# akabeacon_square.net
KiCad netlist of a schematic drawn in EAGLE
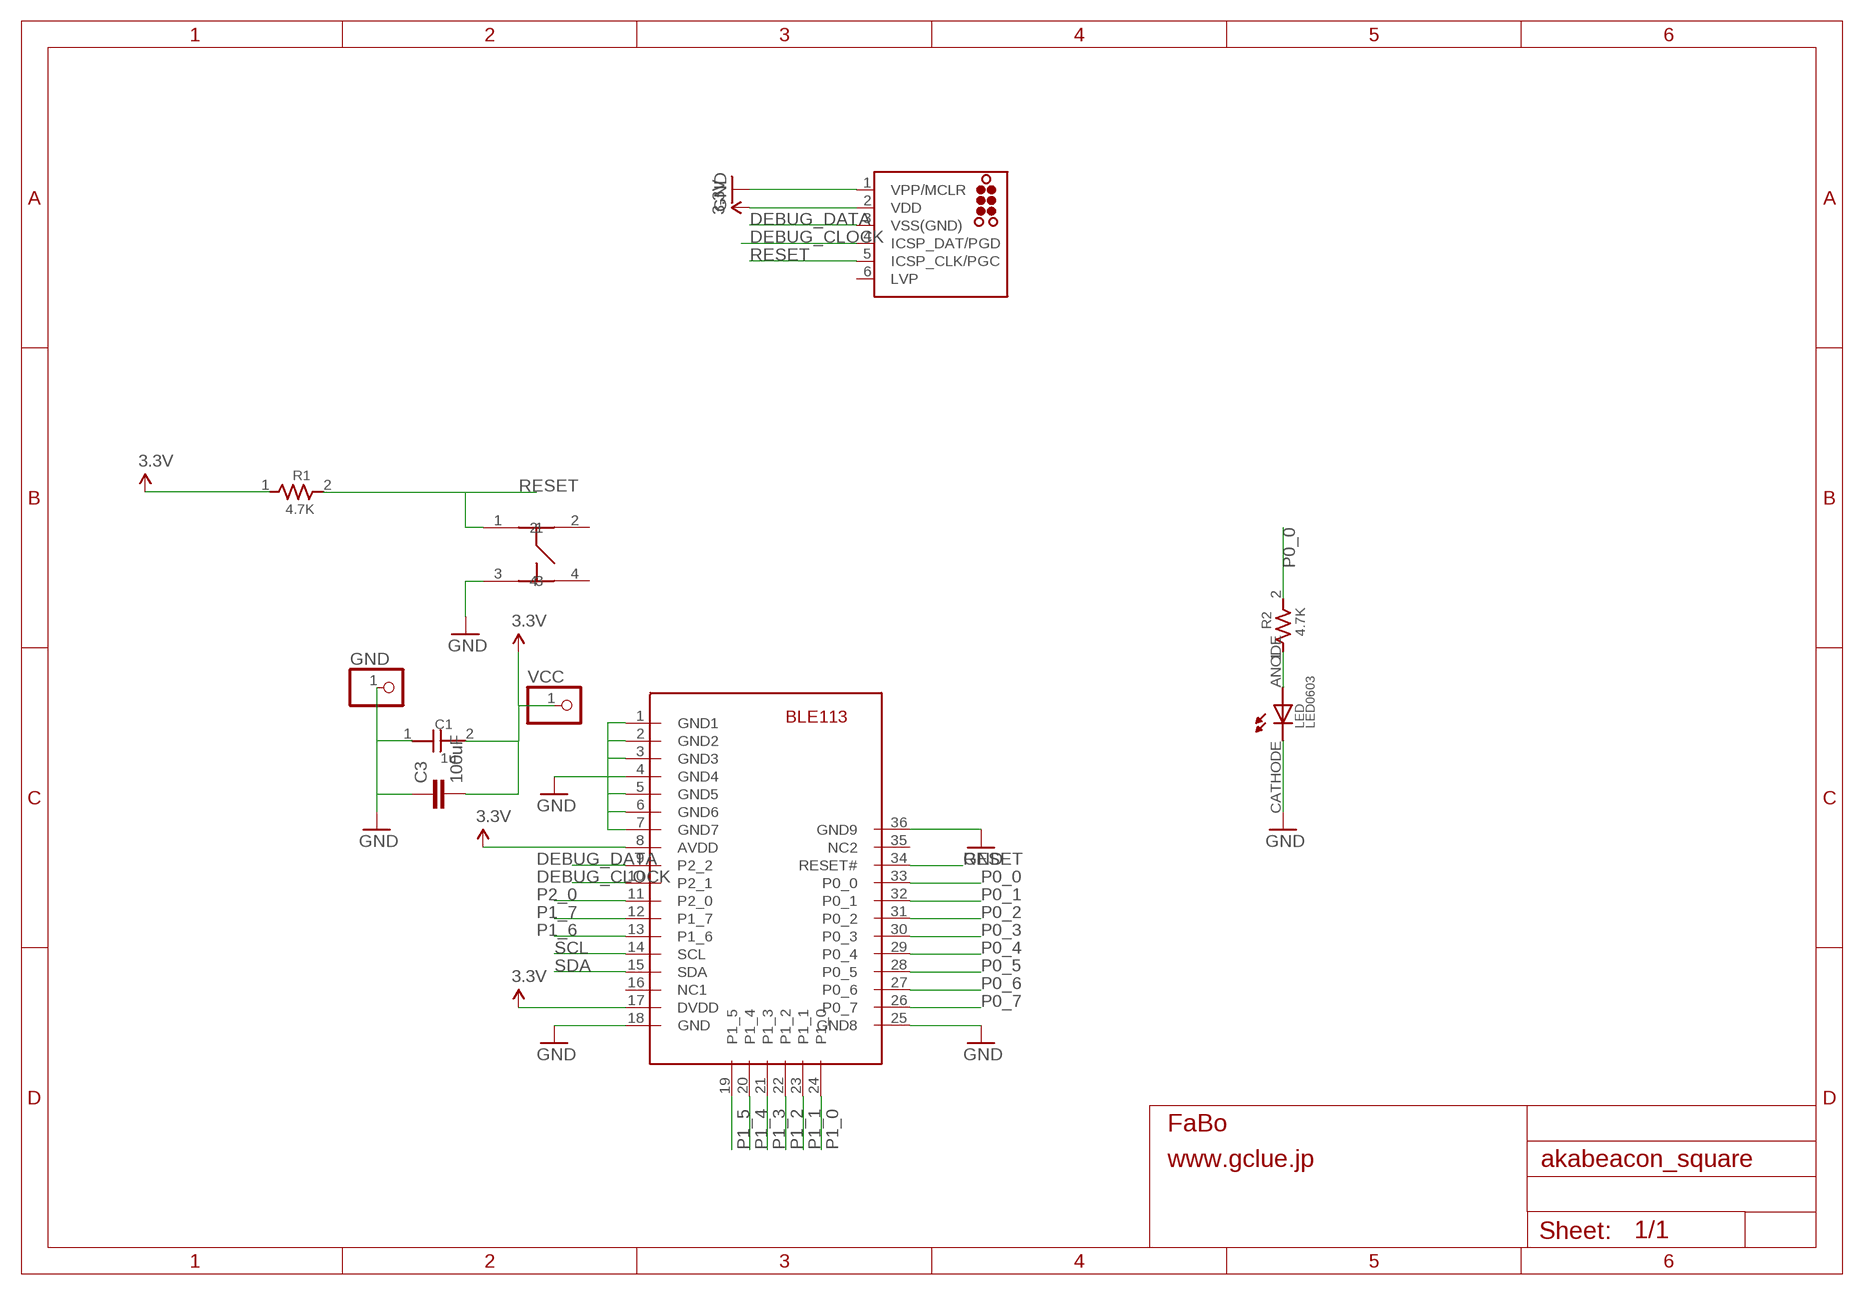
[diagram p0: schematic, sheet 1]

(export (version "E")
  (design (tool "Eeschema 10.0.6"))
  (components
    (comp (ref "C1")
      (value "1u")
      (footprint "eagle-import:0603")
      (libsource (lib "eagle-import") (part "CAPACITOR0603"))
    )
    (comp (ref "C3")
      (value "100uF")
      (footprint "eagle-import:1206")
      (libsource (lib "eagle-import") (part "10UF-6.3V-20%(1206)"))
    )
    (comp (ref "GND")
      (value "PINHD-1X1CB")
      (footprint "eagle-import:1X01-CLEANBIG")
      (libsource (lib "eagle-import") (part "PINHD-1X1CB"))
    )
    (comp (ref "J1")
      (value "TC2030-MCP")
      (footprint "eagle-import:TC2030-MCP")
      (libsource (lib "eagle-import") (part "TC2030-MCP"))
    )
    (comp (ref "LED")
      (value "LED0603")
      (footprint "eagle-import:0603")
      (libsource (lib "eagle-import") (part "LED0603"))
    )
    (comp (ref "R1")
      (value "4.7K")
      (footprint "eagle-import:0603")
      (libsource (lib "eagle-import") (part "RESISTOR0603"))
    )
    (comp (ref "R2")
      (value "4.7K")
      (footprint "eagle-import:0603")
      (libsource (lib "eagle-import") (part "RESISTOR0603"))
    )
    (comp (ref "U$5")
      (value "BLE113")
      (footprint "eagle-import:BLE113")
      (libsource (lib "eagle-import") (part "BLE113"))
    )
    (comp (ref "U$6")
      (value "SWICTH-4P(KMR2)")
      (footprint "eagle-import:SWITCH-4P(KMR2)")
      (libsource (lib "eagle-import") (part "SWICTH-4P(KMR2)"))
    )
    (comp (ref "VCC")
      (value "PINHD-1X1CB")
      (footprint "eagle-import:1X01-CLEANBIG")
      (libsource (lib "eagle-import") (part "PINHD-1X1CB"))
    )
  )
  (nets
    (net (code "1") (name "/DEBUG_CLOCK") (class "Default")
      (node (ref "J1") (pin "4") (pinfunction "ICSP_DAT/PGD_4") (pintype "bidirectional"))
      (node (ref "U$5") (pin "10") (pinfunction "P2_1_10") (pintype "bidirectional"))
    )
    (net (code "2") (name "/DEBUG_DATA") (class "Default")
      (node (ref "J1") (pin "3") (pinfunction "VSS(GND)_3") (pintype "power_in"))
      (node (ref "U$5") (pin "9") (pinfunction "P2_2_9") (pintype "bidirectional"))
    )
    (net (code "3") (name "/P0_0") (class "Default")
      (node (ref "R2") (pin "2") (pinfunction "2_2") (pintype "passive"))
      (node (ref "U$5") (pin "33") (pinfunction "P0_0_33") (pintype "bidirectional"))
    )
    (net (code "4") (name "/P0_1") (class "Default")
      (node (ref "U$5") (pin "32") (pinfunction "P0_1_32") (pintype "bidirectional"))
    )
    (net (code "5") (name "/P0_2") (class "Default")
      (node (ref "U$5") (pin "31") (pinfunction "P0_2_31") (pintype "bidirectional"))
    )
    (net (code "6") (name "/P0_3") (class "Default")
      (node (ref "U$5") (pin "30") (pinfunction "P0_3_30") (pintype "bidirectional"))
    )
    (net (code "7") (name "/P0_4") (class "Default")
      (node (ref "U$5") (pin "29") (pinfunction "P0_4_29") (pintype "bidirectional"))
    )
    (net (code "8") (name "/P0_5") (class "Default")
      (node (ref "U$5") (pin "28") (pinfunction "P0_5_28") (pintype "bidirectional"))
    )
    (net (code "9") (name "/P0_6") (class "Default")
      (node (ref "U$5") (pin "27") (pinfunction "P0_6_27") (pintype "bidirectional"))
    )
    (net (code "10") (name "/P0_7") (class "Default")
      (node (ref "U$5") (pin "26") (pinfunction "P0_7_26") (pintype "bidirectional"))
    )
    (net (code "11") (name "/P1_0") (class "Default")
      (node (ref "U$5") (pin "24") (pinfunction "P1_0_24") (pintype "bidirectional"))
    )
    (net (code "12") (name "/P1_1") (class "Default")
      (node (ref "U$5") (pin "23") (pinfunction "P1_1_23") (pintype "bidirectional"))
    )
    (net (code "13") (name "/P1_2") (class "Default")
      (node (ref "U$5") (pin "22") (pinfunction "P1_2_22") (pintype "bidirectional"))
    )
    (net (code "14") (name "/P1_3") (class "Default")
      (node (ref "U$5") (pin "21") (pinfunction "P1_3_21") (pintype "bidirectional"))
    )
    (net (code "15") (name "/P1_4") (class "Default")
      (node (ref "U$5") (pin "20") (pinfunction "P1_4_20") (pintype "bidirectional"))
    )
    (net (code "16") (name "/P1_5") (class "Default")
      (node (ref "U$5") (pin "19") (pinfunction "P1_5_19") (pintype "bidirectional"))
    )
    (net (code "17") (name "/P1_6") (class "Default")
      (node (ref "U$5") (pin "13") (pinfunction "P1_6_13") (pintype "bidirectional"))
    )
    (net (code "18") (name "/P1_7") (class "Default")
      (node (ref "U$5") (pin "12") (pinfunction "P1_7_12") (pintype "bidirectional"))
    )
    (net (code "19") (name "/P2_0") (class "Default")
      (node (ref "U$5") (pin "11") (pinfunction "P2_0_11") (pintype "bidirectional"))
    )
    (net (code "20") (name "/RESET") (class "Default")
      (node (ref "J1") (pin "5") (pinfunction "ICSP_CLK/PGC_5") (pintype "output"))
      (node (ref "R1") (pin "2") (pinfunction "2_2") (pintype "passive"))
      (node (ref "U$5") (pin "34") (pinfunction "RESET#_34") (pintype "bidirectional"))
      (node (ref "U$6") (pin "1") (pinfunction "1_1") (pintype "bidirectional"))
    )
    (net (code "21") (name "/SCL") (class "Default")
      (node (ref "U$5") (pin "14") (pinfunction "SCL_14") (pintype "bidirectional"))
    )
    (net (code "22") (name "/SDA") (class "Default")
      (node (ref "U$5") (pin "15") (pinfunction "SDA_15") (pintype "bidirectional"))
    )
    (net (code "23") (name "3.3V") (class "Default")
      (node (ref "C1") (pin "2") (pinfunction "2_2") (pintype "passive"))
      (node (ref "C3") (pin "2") (pinfunction "2_2") (pintype "passive"))
      (node (ref "J1") (pin "2") (pinfunction "VDD_2") (pintype "power_in"))
      (node (ref "R1") (pin "1") (pinfunction "1_1") (pintype "passive"))
      (node (ref "U$5") (pin "17") (pinfunction "DVDD_17") (pintype "bidirectional"))
      (node (ref "U$5") (pin "8") (pinfunction "AVDD_8") (pintype "bidirectional"))
      (node (ref "VCC") (pin "1") (pinfunction "1_1") (pintype "passive"))
    )
    (net (code "24") (name "GND") (class "Default")
      (node (ref "C1") (pin "1") (pinfunction "1_1") (pintype "passive"))
      (node (ref "C3") (pin "1") (pinfunction "1_1") (pintype "passive"))
      (node (ref "GND") (pin "1") (pinfunction "1_1") (pintype "passive"))
      (node (ref "J1") (pin "1") (pinfunction "VPP/MCLR_1") (pintype "passive"))
      (node (ref "LED") (pin "CATHODE") (pinfunction "CATHODE_CATHODE") (pintype "passive"))
      (node (ref "U$5") (pin "1") (pinfunction "GND1_1") (pintype "bidirectional"))
      (node (ref "U$5") (pin "18") (pinfunction "GND_18") (pintype "bidirectional"))
      (node (ref "U$5") (pin "2") (pinfunction "GND2_2") (pintype "bidirectional"))
      (node (ref "U$5") (pin "25") (pinfunction "GND8_25") (pintype "bidirectional"))
      (node (ref "U$5") (pin "3") (pinfunction "GND3_3") (pintype "bidirectional"))
      (node (ref "U$5") (pin "36") (pinfunction "GND9_36") (pintype "bidirectional"))
      (node (ref "U$5") (pin "4") (pinfunction "GND4_4") (pintype "bidirectional"))
      (node (ref "U$5") (pin "5") (pinfunction "GND5_5") (pintype "bidirectional"))
      (node (ref "U$5") (pin "6") (pinfunction "GND6_6") (pintype "bidirectional"))
      (node (ref "U$5") (pin "7") (pinfunction "GND7_7") (pintype "bidirectional"))
      (node (ref "U$6") (pin "3") (pinfunction "3_3") (pintype "bidirectional"))
    )
    (net (code "25") (name "Net-(LED-PadANODE)") (class "Default")
      (node (ref "LED") (pin "ANODE") (pinfunction "ANODE_ANODE") (pintype "passive"))
      (node (ref "R2") (pin "1") (pinfunction "1_1") (pintype "passive"))
    )
    (net (code "26") (name "unconnected-(J1-LVP-Pad6)") (class "Default")
      (node (ref "J1") (pin "6") (pinfunction "LVP_6") (pintype "bidirectional"))
    )
    (net (code "27") (name "unconnected-(U$5-NC1-Pad16)") (class "Default")
      (node (ref "U$5") (pin "16") (pinfunction "NC1_16") (pintype "bidirectional"))
    )
    (net (code "28") (name "unconnected-(U$5-NC2-Pad35)") (class "Default")
      (node (ref "U$5") (pin "35") (pinfunction "NC2_35") (pintype "bidirectional"))
    )
    (net (code "29") (name "unconnected-(U$6-Pad2)") (class "Default")
      (node (ref "U$6") (pin "2") (pinfunction "2_2") (pintype "bidirectional"))
    )
    (net (code "30") (name "unconnected-(U$6-Pad4)") (class "Default")
      (node (ref "U$6") (pin "4") (pinfunction "4_4") (pintype "bidirectional"))
    )
  )
)
